# crt13.net
KiCad netlist of a schematic drawn in EAGLE
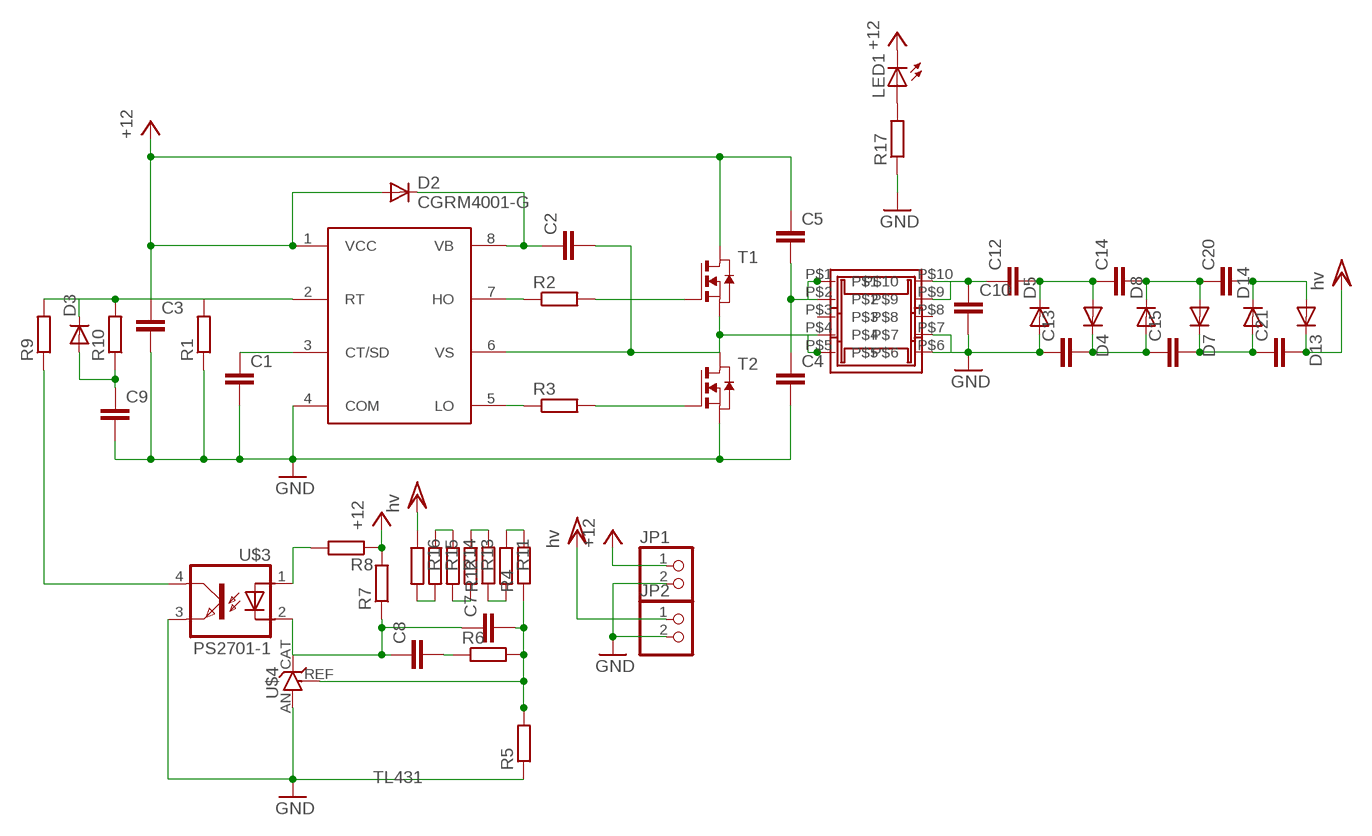
[diagram p0: schematic, sheet 1]

(export (version "E")
  (design (tool "Eeschema 10.0.6"))
  (components
    (comp (ref "C1")
      (value "C-EUC0805")
      (footprint "eagle-import:C0805")
      (libsource (lib "eagle-import") (part "C-EUC0805"))
    )
    (comp (ref "C2")
      (value "C-EUC0805")
      (footprint "eagle-import:C0805")
      (libsource (lib "eagle-import") (part "C-EUC0805"))
    )
    (comp (ref "C3")
      (value "C-EUC1206")
      (footprint "eagle-import:C1206")
      (libsource (lib "eagle-import") (part "C-EUC1206"))
    )
    (comp (ref "C4")
      (value "CC1206")
      (footprint "eagle-import:C1206")
      (libsource (lib "eagle-import") (part "CC1206"))
    )
    (comp (ref "C5")
      (value "CC1206")
      (footprint "eagle-import:C1206")
      (libsource (lib "eagle-import") (part "CC1206"))
    )
    (comp (ref "C7")
      (value "C-EUC0805")
      (footprint "eagle-import:C0805")
      (libsource (lib "eagle-import") (part "C-EUC0805"))
    )
    (comp (ref "C8")
      (value "C-EUC0805")
      (footprint "eagle-import:C0805")
      (libsource (lib "eagle-import") (part "C-EUC0805"))
    )
    (comp (ref "C9")
      (value "C-EUC1206")
      (footprint "eagle-import:C1206")
      (libsource (lib "eagle-import") (part "C-EUC1206"))
    )
    (comp (ref "C10")
      (value "C-EUC1812")
      (footprint "eagle-import:C1812")
      (libsource (lib "eagle-import") (part "C-EUC1812"))
    )
    (comp (ref "C12")
      (value "C-EUC2220K")
      (footprint "eagle-import:C2220K")
      (libsource (lib "eagle-import") (part "C-EUC2220K"))
    )
    (comp (ref "C13")
      (value "C-EUC2220K")
      (footprint "eagle-import:C2220K")
      (libsource (lib "eagle-import") (part "C-EUC2220K"))
    )
    (comp (ref "C14")
      (value "C-EUC2220K")
      (footprint "eagle-import:C2220K")
      (libsource (lib "eagle-import") (part "C-EUC2220K"))
    )
    (comp (ref "C15")
      (value "C-EUC2220K")
      (footprint "eagle-import:C2220K")
      (libsource (lib "eagle-import") (part "C-EUC2220K"))
    )
    (comp (ref "C20")
      (value "C-EUC2220K")
      (footprint "eagle-import:C2220K")
      (libsource (lib "eagle-import") (part "C-EUC2220K"))
    )
    (comp (ref "C21")
      (value "C-EUC2220K")
      (footprint "eagle-import:C2220K")
      (libsource (lib "eagle-import") (part "C-EUC2220K"))
    )
    (comp (ref "D2")
      (value "CGRM4001-G")
      (footprint "eagle-import:SOD-123_MINI-SMA")
      (libsource (lib "eagle-import") (part "CGRM400-G1"))
    )
    (comp (ref "D3")
      (value "DIODE-SOD80C")
      (footprint "eagle-import:SOD80C")
      (libsource (lib "eagle-import") (part "DIODE-SOD80C"))
    )
    (comp (ref "D4")
      (value "DIODE-DO-214AC")
      (footprint "eagle-import:DO-214AC")
      (libsource (lib "eagle-import") (part "DIODE-DO-214AC"))
    )
    (comp (ref "D5")
      (value "DIODE-DO-214AC")
      (footprint "eagle-import:DO-214AC")
      (libsource (lib "eagle-import") (part "DIODE-DO-214AC"))
    )
    (comp (ref "D7")
      (value "DIODE-DO-214AC")
      (footprint "eagle-import:DO-214AC")
      (libsource (lib "eagle-import") (part "DIODE-DO-214AC"))
    )
    (comp (ref "D8")
      (value "DIODE-DO-214AC")
      (footprint "eagle-import:DO-214AC")
      (libsource (lib "eagle-import") (part "DIODE-DO-214AC"))
    )
    (comp (ref "D13")
      (value "DIODE-DO-214AC")
      (footprint "eagle-import:DO-214AC")
      (libsource (lib "eagle-import") (part "DIODE-DO-214AC"))
    )
    (comp (ref "D14")
      (value "DIODE-DO-214AC")
      (footprint "eagle-import:DO-214AC")
      (libsource (lib "eagle-import") (part "DIODE-DO-214AC"))
    )
    (comp (ref "JP1")
      (value "PINHD-1X2")
      (footprint "eagle-import:1X02")
      (libsource (lib "eagle-import") (part "PINHD-1X2"))
    )
    (comp (ref "JP2")
      (value "PINHD-1X2")
      (footprint "eagle-import:1X02")
      (libsource (lib "eagle-import") (part "PINHD-1X2"))
    )
    (comp (ref "LED1")
      (value "LEDCHIP-LED0805")
      (footprint "eagle-import:CHIP-LED0805")
      (libsource (lib "eagle-import") (part "LEDCHIP-LED0805"))
    )
    (comp (ref "R1")
      (value "R-EU_R0805")
      (footprint "eagle-import:R0805")
      (libsource (lib "eagle-import") (part "R-EU_R0805"))
    )
    (comp (ref "R2")
      (value "R-EU_R0805")
      (footprint "eagle-import:R0805")
      (libsource (lib "eagle-import") (part "R-EU_R0805"))
    )
    (comp (ref "R3")
      (value "R-EU_R0805")
      (footprint "eagle-import:R0805")
      (libsource (lib "eagle-import") (part "R-EU_R0805"))
    )
    (comp (ref "R4")
      (value "R-EU_R0805")
      (footprint "eagle-import:R0805")
      (libsource (lib "eagle-import") (part "R-EU_R0805"))
    )
    (comp (ref "R5")
      (value "R-EU_R0805")
      (footprint "eagle-import:R0805")
      (libsource (lib "eagle-import") (part "R-EU_R0805"))
    )
    (comp (ref "R6")
      (value "R-EU_R0805")
      (footprint "eagle-import:R0805")
      (libsource (lib "eagle-import") (part "R-EU_R0805"))
    )
    (comp (ref "R7")
      (value "R-EU_R0805")
      (footprint "eagle-import:R0805")
      (libsource (lib "eagle-import") (part "R-EU_R0805"))
    )
    (comp (ref "R8")
      (value "R-EU_R0805")
      (footprint "eagle-import:R0805")
      (libsource (lib "eagle-import") (part "R-EU_R0805"))
    )
    (comp (ref "R9")
      (value "R-EU_R0805")
      (footprint "eagle-import:R0805")
      (libsource (lib "eagle-import") (part "R-EU_R0805"))
    )
    (comp (ref "R10")
      (value "R-EU_R0805")
      (footprint "eagle-import:R0805")
      (libsource (lib "eagle-import") (part "R-EU_R0805"))
    )
    (comp (ref "R11")
      (value "R-EU_R0805")
      (footprint "eagle-import:R0805")
      (libsource (lib "eagle-import") (part "R-EU_R0805"))
    )
    (comp (ref "R12")
      (value "R-EU_R0805")
      (footprint "eagle-import:R0805")
      (libsource (lib "eagle-import") (part "R-EU_R0805"))
    )
    (comp (ref "R13")
      (value "R-EU_R0805")
      (footprint "eagle-import:R0805")
      (libsource (lib "eagle-import") (part "R-EU_R0805"))
    )
    (comp (ref "R14")
      (value "R-EU_R0805")
      (footprint "eagle-import:R0805")
      (libsource (lib "eagle-import") (part "R-EU_R0805"))
    )
    (comp (ref "R15")
      (value "R-EU_R0805")
      (footprint "eagle-import:R0805")
      (libsource (lib "eagle-import") (part "R-EU_R0805"))
    )
    (comp (ref "R16")
      (value "R-EU_R0805")
      (footprint "eagle-import:R0805")
      (libsource (lib "eagle-import") (part "R-EU_R0805"))
    )
    (comp (ref "R17")
      (value "R-EU_R0805")
      (footprint "eagle-import:R0805")
      (libsource (lib "eagle-import") (part "R-EU_R0805"))
    )
    (comp (ref "T1")
      (value "NMOSSOT23")
      (footprint "eagle-import:SOT-23")
      (libsource (lib "eagle-import") (part "NMOSSOT23"))
    )
    (comp (ref "T2")
      (value "NMOSSOT23")
      (footprint "eagle-import:SOT-23")
      (libsource (lib "eagle-import") (part "NMOSSOT23"))
    )
    (comp (ref "U$1")
      (value "IRS2795")
      (footprint "eagle-import:SO08")
      (libsource (lib "eagle-import") (part "IRS2795"))
    )
    (comp (ref "U$2")
      (value "EFD15-K-10P")
      (footprint "eagle-import:EFD15-K10P")
      (libsource (lib "eagle-import") (part "EFD15-K-10P"))
    )
    (comp (ref "U$3")
      (value "PS2701-1")
      (footprint "eagle-import:SOP04")
      (libsource (lib "eagle-import") (part "PS2701-1"))
    )
    (comp (ref "U$4")
      (value "TL431")
      (footprint "eagle-import:SOT23")
      (libsource (lib "eagle-import") (part "TL431"))
    )
  )
  (nets
    (net (code "1") (name "+12") (class "Default")
      (node (ref "C3") (pin "1") (pinfunction "1_1") (pintype "passive"))
      (node (ref "C5") (pin "1") (pinfunction "1_1") (pintype "passive"))
      (node (ref "D2") (pin "A") (pinfunction "A_A") (pintype "passive"))
      (node (ref "JP1") (pin "1") (pinfunction "1_1") (pintype "passive"))
      (node (ref "LED1") (pin "C") (pinfunction "C_C") (pintype "passive"))
      (node (ref "R7") (pin "2") (pinfunction "2_2") (pintype "passive"))
      (node (ref "R8") (pin "1") (pinfunction "1_1") (pintype "passive"))
      (node (ref "T1") (pin "1") (pinfunction "D_1") (pintype "passive"))
      (node (ref "U$1") (pin "1") (pinfunction "VCC_1") (pintype "bidirectional"))
    )
    (net (code "2") (name "GND") (class "Default")
      (node (ref "C1") (pin "2") (pinfunction "2_2") (pintype "passive"))
      (node (ref "C10") (pin "2") (pinfunction "2_2") (pintype "passive"))
      (node (ref "C13") (pin "1") (pinfunction "1_1") (pintype "passive"))
      (node (ref "C3") (pin "2") (pinfunction "2_2") (pintype "passive"))
      (node (ref "C4") (pin "2") (pinfunction "2_2") (pintype "passive"))
      (node (ref "C9") (pin "2") (pinfunction "2_2") (pintype "passive"))
      (node (ref "D5") (pin "A") (pinfunction "A_A") (pintype "passive"))
      (node (ref "JP1") (pin "2") (pinfunction "2_2") (pintype "passive"))
      (node (ref "JP2") (pin "2") (pinfunction "2_2") (pintype "passive"))
      (node (ref "R1") (pin "1") (pinfunction "1_1") (pintype "passive"))
      (node (ref "R17") (pin "1") (pinfunction "1_1") (pintype "passive"))
      (node (ref "R5") (pin "1") (pinfunction "1_1") (pintype "passive"))
      (node (ref "T2") (pin "2") (pinfunction "S_2") (pintype "passive"))
      (node (ref "U$1") (pin "4") (pinfunction "COM_4") (pintype "bidirectional"))
      (node (ref "U$2") (pin "P$6") (pinfunction "P$6_P$6") (pintype "bidirectional"))
      (node (ref "U$2") (pin "P$7") (pinfunction "P$7_P$7") (pintype "bidirectional"))
      (node (ref "U$3") (pin "3") (pinfunction "3_3") (pintype "passive"))
      (node (ref "U$4") (pin "AN") (pinfunction "AN_AN") (pintype "passive"))
    )
    (net (code "3") (name "Net-(C4-Pad1)") (class "Default")
      (node (ref "C4") (pin "1") (pinfunction "1_1") (pintype "passive"))
      (node (ref "C5") (pin "2") (pinfunction "2_2") (pintype "passive"))
      (node (ref "U$2") (pin "P$1") (pinfunction "P$1_P$1") (pintype "bidirectional"))
      (node (ref "U$2") (pin "P$2") (pinfunction "P$2_P$2") (pintype "bidirectional"))
    )
    (net (code "4") (name "Net-(C7-Pad1)") (class "Default")
      (node (ref "C7") (pin "1") (pinfunction "1_1") (pintype "passive"))
      (node (ref "C8") (pin "1") (pinfunction "1_1") (pintype "passive"))
      (node (ref "R7") (pin "1") (pinfunction "1_1") (pintype "passive"))
      (node (ref "U$3") (pin "2") (pinfunction "2_2") (pintype "passive"))
      (node (ref "U$4") (pin "CAT") (pinfunction "CAT_CAT") (pintype "passive"))
    )
    (net (code "5") (name "Net-(C7-Pad2)") (class "Default")
      (node (ref "C7") (pin "2") (pinfunction "2_2") (pintype "passive"))
      (node (ref "R4") (pin "1") (pinfunction "1_1") (pintype "passive"))
      (node (ref "R5") (pin "2") (pinfunction "2_2") (pintype "passive"))
      (node (ref "R6") (pin "2") (pinfunction "2_2") (pintype "passive"))
      (node (ref "U$4") (pin "REF") (pinfunction "REF_REF") (pintype "passive"))
    )
    (net (code "6") (name "Net-(C8-Pad2)") (class "Default")
      (node (ref "C8") (pin "2") (pinfunction "2_2") (pintype "passive"))
      (node (ref "R6") (pin "1") (pinfunction "1_1") (pintype "passive"))
    )
    (net (code "7") (name "Net-(C9-Pad1)") (class "Default")
      (node (ref "C9") (pin "1") (pinfunction "1_1") (pintype "passive"))
      (node (ref "D3") (pin "A") (pinfunction "A_A") (pintype "passive"))
      (node (ref "R10") (pin "1") (pinfunction "1_1") (pintype "passive"))
    )
    (net (code "8") (name "Net-(C10-Pad1)") (class "Default")
      (node (ref "C10") (pin "1") (pinfunction "1_1") (pintype "passive"))
      (node (ref "C12") (pin "1") (pinfunction "1_1") (pintype "passive"))
      (node (ref "U$2") (pin "P$10") (pinfunction "P$10_P$10") (pintype "bidirectional"))
      (node (ref "U$2") (pin "P$9") (pinfunction "P$9_P$9") (pintype "bidirectional"))
    )
    (net (code "9") (name "Net-(C12-Pad2)") (class "Default")
      (node (ref "C12") (pin "2") (pinfunction "2_2") (pintype "passive"))
      (node (ref "C14") (pin "1") (pinfunction "1_1") (pintype "passive"))
      (node (ref "D4") (pin "A") (pinfunction "A_A") (pintype "passive"))
      (node (ref "D5") (pin "C") (pinfunction "C_C") (pintype "passive"))
    )
    (net (code "10") (name "Net-(C13-Pad2)") (class "Default")
      (node (ref "C13") (pin "2") (pinfunction "2_2") (pintype "passive"))
      (node (ref "C15") (pin "1") (pinfunction "1_1") (pintype "passive"))
      (node (ref "D4") (pin "C") (pinfunction "C_C") (pintype "passive"))
      (node (ref "D8") (pin "A") (pinfunction "A_A") (pintype "passive"))
    )
    (net (code "11") (name "Net-(C14-Pad2)") (class "Default")
      (node (ref "C14") (pin "2") (pinfunction "2_2") (pintype "passive"))
      (node (ref "C20") (pin "1") (pinfunction "1_1") (pintype "passive"))
      (node (ref "D7") (pin "A") (pinfunction "A_A") (pintype "passive"))
      (node (ref "D8") (pin "C") (pinfunction "C_C") (pintype "passive"))
    )
    (net (code "12") (name "Net-(C15-Pad2)") (class "Default")
      (node (ref "C15") (pin "2") (pinfunction "2_2") (pintype "passive"))
      (node (ref "C21") (pin "1") (pinfunction "1_1") (pintype "passive"))
      (node (ref "D14") (pin "A") (pinfunction "A_A") (pintype "passive"))
      (node (ref "D7") (pin "C") (pinfunction "C_C") (pintype "passive"))
    )
    (net (code "13") (name "Net-(C20-Pad2)") (class "Default")
      (node (ref "C20") (pin "2") (pinfunction "2_2") (pintype "passive"))
      (node (ref "D13") (pin "A") (pinfunction "A_A") (pintype "passive"))
      (node (ref "D14") (pin "C") (pinfunction "C_C") (pintype "passive"))
    )
    (net (code "14") (name "Net-(LED1-PadA)") (class "Default")
      (node (ref "LED1") (pin "A") (pinfunction "A_A") (pintype "passive"))
      (node (ref "R17") (pin "2") (pinfunction "2_2") (pintype "passive"))
    )
    (net (code "15") (name "Net-(R8-Pad2)") (class "Default")
      (node (ref "R8") (pin "2") (pinfunction "2_2") (pintype "passive"))
      (node (ref "U$3") (pin "1") (pinfunction "1_1") (pintype "passive"))
    )
    (net (code "16") (name "Net-(R9-Pad1)") (class "Default")
      (node (ref "R9") (pin "1") (pinfunction "1_1") (pintype "passive"))
      (node (ref "U$3") (pin "4") (pinfunction "4_4") (pintype "passive"))
    )
    (net (code "17") (name "Net-(R11-Pad1)") (class "Default")
      (node (ref "R11") (pin "1") (pinfunction "1_1") (pintype "passive"))
      (node (ref "R4") (pin "2") (pinfunction "2_2") (pintype "passive"))
    )
    (net (code "18") (name "Net-(R11-Pad2)") (class "Default")
      (node (ref "R11") (pin "2") (pinfunction "2_2") (pintype "passive"))
      (node (ref "R12") (pin "1") (pinfunction "1_1") (pintype "passive"))
    )
    (net (code "19") (name "Net-(R12-Pad2)") (class "Default")
      (node (ref "R12") (pin "2") (pinfunction "2_2") (pintype "passive"))
      (node (ref "R13") (pin "1") (pinfunction "1_1") (pintype "passive"))
    )
    (net (code "20") (name "Net-(R13-Pad2)") (class "Default")
      (node (ref "R13") (pin "2") (pinfunction "2_2") (pintype "passive"))
      (node (ref "R14") (pin "2") (pinfunction "2_2") (pintype "passive"))
    )
    (net (code "21") (name "Net-(R14-Pad1)") (class "Default")
      (node (ref "R14") (pin "1") (pinfunction "1_1") (pintype "passive"))
      (node (ref "R15") (pin "1") (pinfunction "1_1") (pintype "passive"))
    )
    (net (code "22") (name "Net-(R15-Pad2)") (class "Default")
      (node (ref "R15") (pin "2") (pinfunction "2_2") (pintype "passive"))
      (node (ref "R16") (pin "2") (pinfunction "2_2") (pintype "passive"))
    )
    (net (code "23") (name "Net-(T1-G)") (class "Default")
      (node (ref "R2") (pin "2") (pinfunction "2_2") (pintype "passive"))
      (node (ref "T1") (pin "3") (pinfunction "G_3") (pintype "passive"))
    )
    (net (code "24") (name "Net-(T1-S)") (class "Default")
      (node (ref "C2") (pin "2") (pinfunction "2_2") (pintype "passive"))
      (node (ref "T1") (pin "2") (pinfunction "S_2") (pintype "passive"))
      (node (ref "T2") (pin "1") (pinfunction "D_1") (pintype "passive"))
      (node (ref "U$1") (pin "6") (pinfunction "VS_6") (pintype "bidirectional"))
      (node (ref "U$2") (pin "P$4") (pinfunction "P$4_P$4") (pintype "bidirectional"))
      (node (ref "U$2") (pin "P$5") (pinfunction "P$5_P$5") (pintype "bidirectional"))
    )
    (net (code "25") (name "Net-(T2-G)") (class "Default")
      (node (ref "R3") (pin "2") (pinfunction "2_2") (pintype "passive"))
      (node (ref "T2") (pin "3") (pinfunction "G_3") (pintype "passive"))
    )
    (net (code "26") (name "Net-(U$1-CT{slash}SD)") (class "Default")
      (node (ref "C1") (pin "1") (pinfunction "1_1") (pintype "passive"))
      (node (ref "U$1") (pin "3") (pinfunction "CT/SD_3") (pintype "bidirectional"))
    )
    (net (code "27") (name "Net-(U$1-HO)") (class "Default")
      (node (ref "R2") (pin "1") (pinfunction "1_1") (pintype "passive"))
      (node (ref "U$1") (pin "7") (pinfunction "HO_7") (pintype "output"))
    )
    (net (code "28") (name "Net-(U$1-LO)") (class "Default")
      (node (ref "R3") (pin "1") (pinfunction "1_1") (pintype "passive"))
      (node (ref "U$1") (pin "5") (pinfunction "LO_5") (pintype "output"))
    )
    (net (code "29") (name "Net-(U$1-RT)") (class "Default")
      (node (ref "D3") (pin "C") (pinfunction "C_C") (pintype "passive"))
      (node (ref "R1") (pin "2") (pinfunction "2_2") (pintype "passive"))
      (node (ref "R10") (pin "2") (pinfunction "2_2") (pintype "passive"))
      (node (ref "R9") (pin "2") (pinfunction "2_2") (pintype "passive"))
      (node (ref "U$1") (pin "2") (pinfunction "RT_2") (pintype "bidirectional"))
    )
    (net (code "30") (name "Net-(U$1-VB)") (class "Default")
      (node (ref "C2") (pin "1") (pinfunction "1_1") (pintype "passive"))
      (node (ref "D2") (pin "C") (pinfunction "C_C") (pintype "passive"))
      (node (ref "U$1") (pin "8") (pinfunction "VB_8") (pintype "bidirectional"))
    )
    (net (code "31") (name "hv") (class "Default")
      (node (ref "C21") (pin "2") (pinfunction "2_2") (pintype "passive"))
      (node (ref "D13") (pin "C") (pinfunction "C_C") (pintype "passive"))
      (node (ref "JP2") (pin "1") (pinfunction "1_1") (pintype "passive"))
      (node (ref "R16") (pin "1") (pinfunction "1_1") (pintype "passive"))
    )
    (net (code "32") (name "unconnected-(U$2-PadP$3)") (class "Default")
      (node (ref "U$2") (pin "P$3") (pinfunction "P$3_P$3") (pintype "bidirectional"))
    )
    (net (code "33") (name "unconnected-(U$2-PadP$8)") (class "Default")
      (node (ref "U$2") (pin "P$8") (pinfunction "P$8_P$8") (pintype "bidirectional"))
    )
  )
)
